# AudioStream_v2.net
KiCad netlist of a schematic drawn in EAGLE
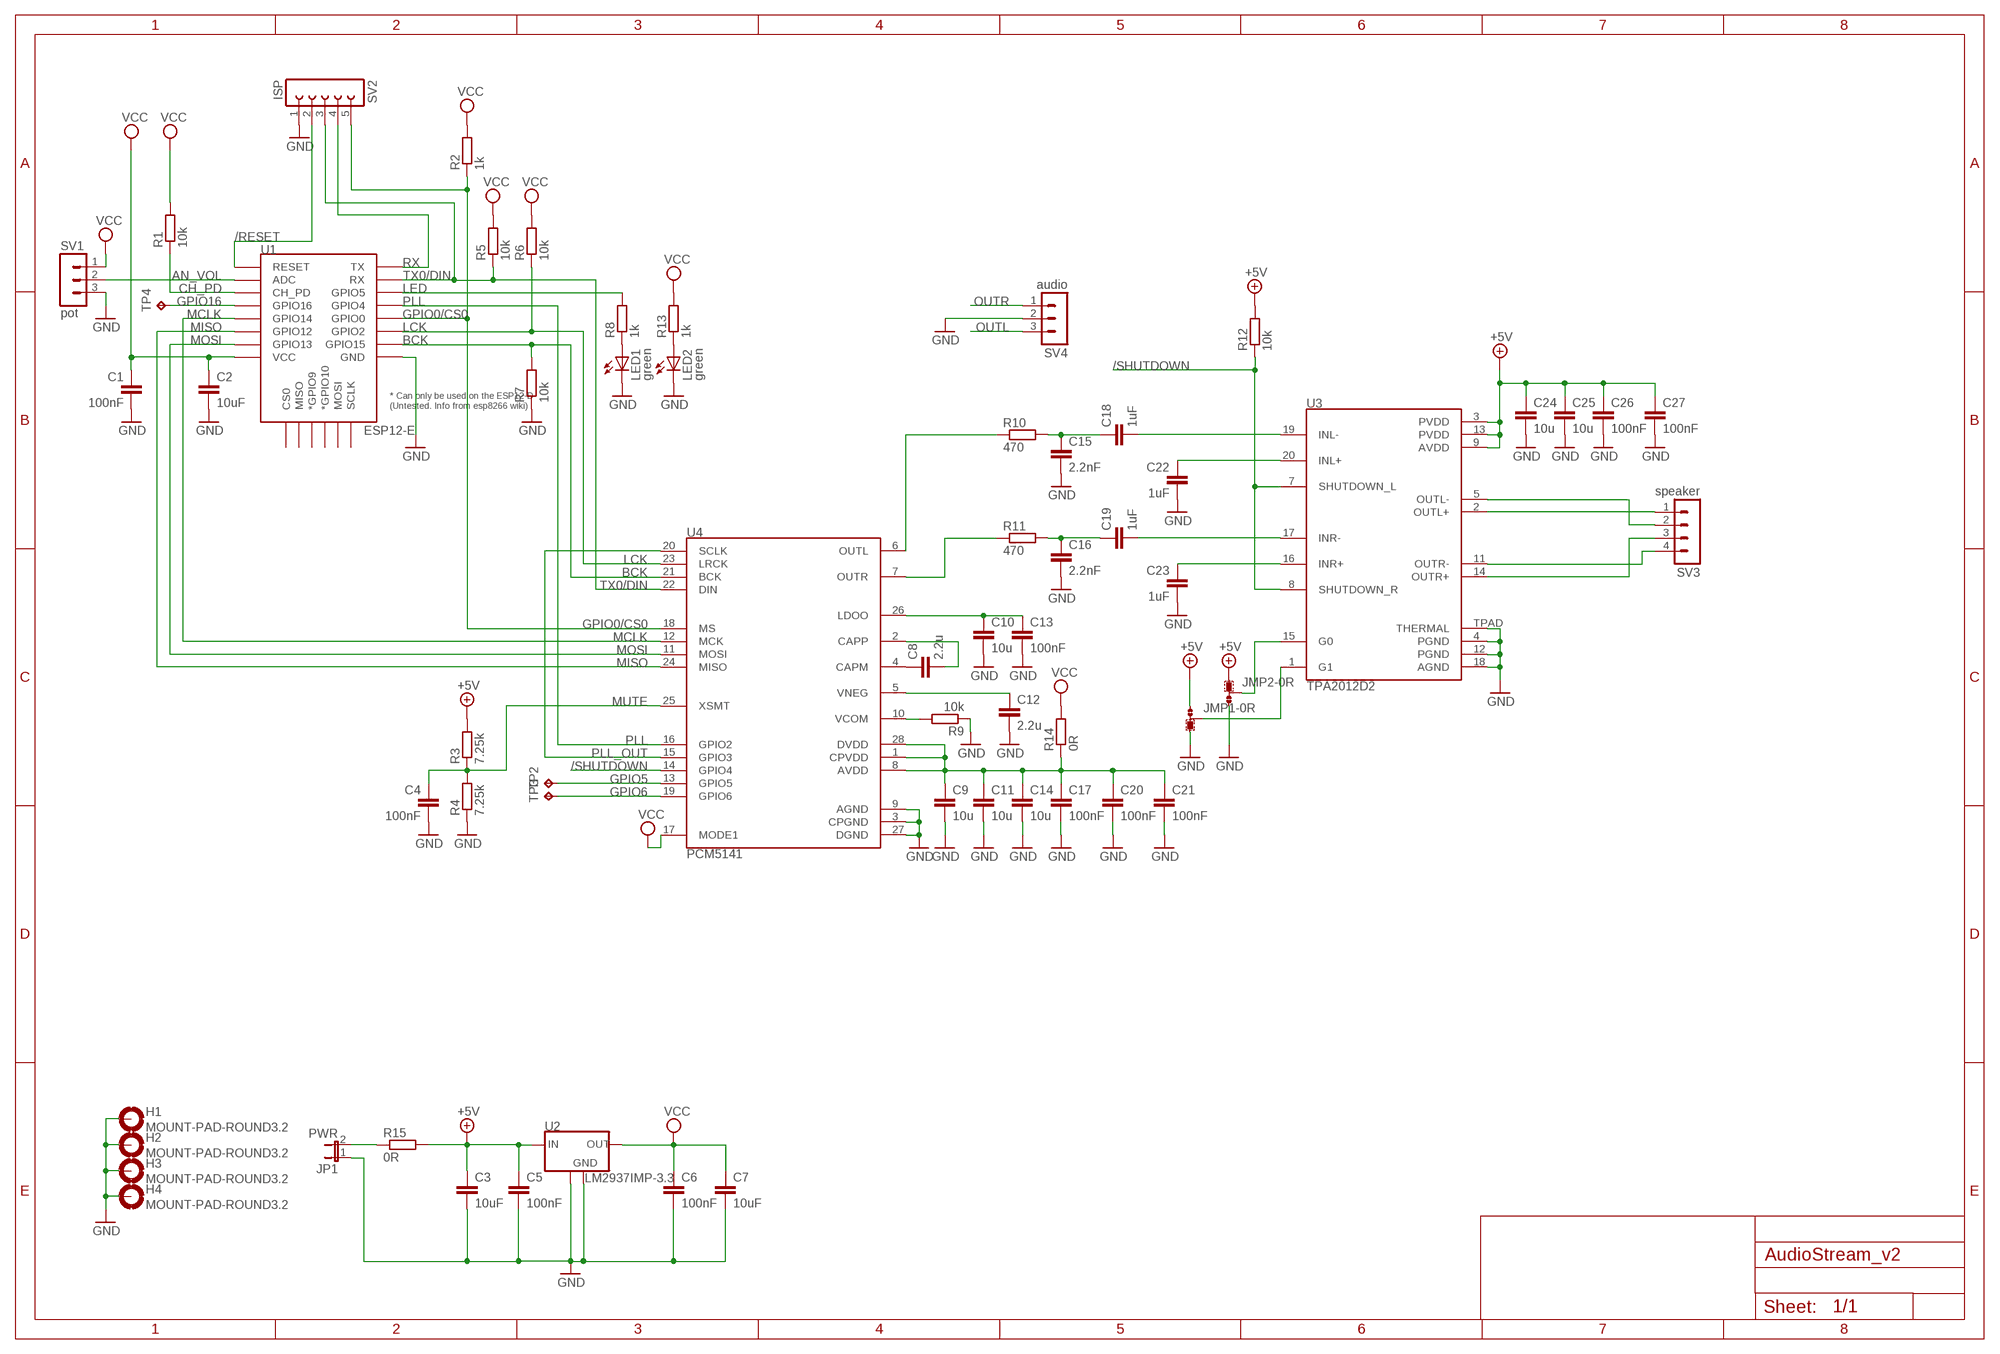
[diagram p0: schematic, sheet 1]

(export (version "E")
  (design (tool "Eeschema 10.0.6"))
  (components
    (comp (ref "C1")
      (value "100nF")
      (footprint "eagle-import:C0805")
      (libsource (lib "eagle-import") (part "C-EUC0805"))
    )
    (comp (ref "C2")
      (value "10uF")
      (footprint "eagle-import:C1210")
      (libsource (lib "eagle-import") (part "C-EUC1210"))
    )
    (comp (ref "C3")
      (value "10uF")
      (footprint "eagle-import:C3216")
      (libsource (lib "eagle-import") (part "C-EUC3216"))
    )
    (comp (ref "C4")
      (value "100nF")
      (footprint "eagle-import:C0603")
      (libsource (lib "eagle-import") (part "C-EUC0603"))
    )
    (comp (ref "C5")
      (value "100nF")
      (footprint "eagle-import:C0805")
      (libsource (lib "eagle-import") (part "C-EUC0805"))
    )
    (comp (ref "C6")
      (value "100nF")
      (footprint "eagle-import:C0805")
      (libsource (lib "eagle-import") (part "C-EUC0805"))
    )
    (comp (ref "C7")
      (value "10uF")
      (footprint "eagle-import:C3216")
      (libsource (lib "eagle-import") (part "C-EUC3216"))
    )
    (comp (ref "C8")
      (value "2.2u")
      (footprint "eagle-import:C0805")
      (libsource (lib "eagle-import") (part "C-EUC0805"))
    )
    (comp (ref "C9")
      (value "10u")
      (footprint "eagle-import:C3216")
      (libsource (lib "eagle-import") (part "C-EUC3216"))
    )
    (comp (ref "C10")
      (value "10u")
      (footprint "eagle-import:C3216")
      (libsource (lib "eagle-import") (part "C-EUC3216"))
    )
    (comp (ref "C11")
      (value "10u")
      (footprint "eagle-import:C3216")
      (libsource (lib "eagle-import") (part "C-EUC3216"))
    )
    (comp (ref "C12")
      (value "2.2u")
      (footprint "eagle-import:C0805")
      (libsource (lib "eagle-import") (part "C-EUC0805"))
    )
    (comp (ref "C13")
      (value "100nF")
      (footprint "eagle-import:C0805")
      (libsource (lib "eagle-import") (part "C-EUC0805"))
    )
    (comp (ref "C14")
      (value "10u")
      (footprint "eagle-import:C3216")
      (libsource (lib "eagle-import") (part "C-EUC3216"))
    )
    (comp (ref "C15")
      (value "2.2nF")
      (footprint "eagle-import:C0603")
      (libsource (lib "eagle-import") (part "C-EUC0603"))
    )
    (comp (ref "C16")
      (value "2.2nF")
      (footprint "eagle-import:C0603")
      (libsource (lib "eagle-import") (part "C-EUC0603"))
    )
    (comp (ref "C17")
      (value "100nF")
      (footprint "eagle-import:C0805")
      (libsource (lib "eagle-import") (part "C-EUC0805"))
    )
    (comp (ref "C18")
      (value "1uF")
      (footprint "eagle-import:C0805")
      (libsource (lib "eagle-import") (part "C-EUC0805"))
    )
    (comp (ref "C19")
      (value "1uF")
      (footprint "eagle-import:C0805")
      (libsource (lib "eagle-import") (part "C-EUC0805"))
    )
    (comp (ref "C20")
      (value "100nF")
      (footprint "eagle-import:C0805")
      (libsource (lib "eagle-import") (part "C-EUC0805"))
    )
    (comp (ref "C21")
      (value "100nF")
      (footprint "eagle-import:C0805")
      (libsource (lib "eagle-import") (part "C-EUC0805"))
    )
    (comp (ref "C22")
      (value "1uF")
      (footprint "eagle-import:C0805")
      (libsource (lib "eagle-import") (part "C-EUC0805"))
    )
    (comp (ref "C23")
      (value "1uF")
      (footprint "eagle-import:C0805")
      (libsource (lib "eagle-import") (part "C-EUC0805"))
    )
    (comp (ref "C24")
      (value "10u")
      (footprint "eagle-import:C3216")
      (libsource (lib "eagle-import") (part "C-EUC3216"))
    )
    (comp (ref "C25")
      (value "10u")
      (footprint "eagle-import:C3216")
      (libsource (lib "eagle-import") (part "C-EUC3216"))
    )
    (comp (ref "C26")
      (value "100nF")
      (footprint "eagle-import:C0805")
      (libsource (lib "eagle-import") (part "C-EUC0805"))
    )
    (comp (ref "C27")
      (value "100nF")
      (footprint "eagle-import:C0805")
      (libsource (lib "eagle-import") (part "C-EUC0805"))
    )
    (comp (ref "H1")
      (value "MOUNT-PAD-ROUND3.2")
      (footprint "eagle-import:3,2-PAD")
      (libsource (lib "eagle-import") (part "MOUNT-PAD-ROUND3.2"))
    )
    (comp (ref "H2")
      (value "MOUNT-PAD-ROUND3.2")
      (footprint "eagle-import:3,2-PAD")
      (libsource (lib "eagle-import") (part "MOUNT-PAD-ROUND3.2"))
    )
    (comp (ref "H3")
      (value "MOUNT-PAD-ROUND3.2")
      (footprint "eagle-import:3,2-PAD")
      (libsource (lib "eagle-import") (part "MOUNT-PAD-ROUND3.2"))
    )
    (comp (ref "H4")
      (value "MOUNT-PAD-ROUND3.2")
      (footprint "eagle-import:3,2-PAD")
      (libsource (lib "eagle-import") (part "MOUNT-PAD-ROUND3.2"))
    )
    (comp (ref "JMP1")
      (value "0R-JUMPA")
      (footprint "eagle-import:A0R-JMP")
      (libsource (lib "eagle-import") (part "0R-JUMPA"))
    )
    (comp (ref "JMP2")
      (value "0R-JUMPA")
      (footprint "eagle-import:A0R-JMP")
      (libsource (lib "eagle-import") (part "0R-JUMPA"))
    )
    (comp (ref "JP1")
      (value "PWR")
      (footprint "eagle-import:JP1")
      (libsource (lib "eagle-import") (part "JP1E"))
    )
    (comp (ref "LED1")
      (value "green")
      (footprint "eagle-import:CHIPLED_0805")
      (libsource (lib "eagle-import") (part "LEDCHIPLED_0805"))
    )
    (comp (ref "LED2")
      (value "green")
      (footprint "eagle-import:CHIPLED_0805")
      (libsource (lib "eagle-import") (part "LEDCHIPLED_0805"))
    )
    (comp (ref "R1")
      (value "10k")
      (footprint "eagle-import:R0603")
      (libsource (lib "eagle-import") (part "R-EU_R0603"))
    )
    (comp (ref "R2")
      (value "1k")
      (footprint "eagle-import:R0603")
      (libsource (lib "eagle-import") (part "R-EU_R0603"))
    )
    (comp (ref "R3")
      (value "7.25k")
      (footprint "eagle-import:R0603")
      (libsource (lib "eagle-import") (part "R-EU_R0603"))
    )
    (comp (ref "R4")
      (value "7.25k")
      (footprint "eagle-import:R0603")
      (libsource (lib "eagle-import") (part "R-EU_R0603"))
    )
    (comp (ref "R5")
      (value "10k")
      (footprint "eagle-import:R0603")
      (libsource (lib "eagle-import") (part "R-EU_R0603"))
    )
    (comp (ref "R6")
      (value "10k")
      (footprint "eagle-import:R0603")
      (libsource (lib "eagle-import") (part "R-EU_R0603"))
    )
    (comp (ref "R7")
      (value "10k")
      (footprint "eagle-import:R0603")
      (libsource (lib "eagle-import") (part "R-EU_R0603"))
    )
    (comp (ref "R8")
      (value "1k")
      (footprint "eagle-import:R0603")
      (libsource (lib "eagle-import") (part "R-EU_R0603"))
    )
    (comp (ref "R9")
      (value "10k")
      (footprint "eagle-import:R0603")
      (libsource (lib "eagle-import") (part "R-EU_R0603"))
    )
    (comp (ref "R10")
      (value "470")
      (footprint "eagle-import:R0603")
      (libsource (lib "eagle-import") (part "R-EU_R0603"))
    )
    (comp (ref "R11")
      (value "470")
      (footprint "eagle-import:R0603")
      (libsource (lib "eagle-import") (part "R-EU_R0603"))
    )
    (comp (ref "R12")
      (value "10k")
      (footprint "eagle-import:R0603")
      (libsource (lib "eagle-import") (part "R-EU_R0603"))
    )
    (comp (ref "R13")
      (value "1k")
      (footprint "eagle-import:R0603")
      (libsource (lib "eagle-import") (part "R-EU_R0603"))
    )
    (comp (ref "R14")
      (value "0R")
      (footprint "eagle-import:R0805")
      (libsource (lib "eagle-import") (part "R-EU_R0805"))
    )
    (comp (ref "R15")
      (value "0R")
      (footprint "eagle-import:R0805")
      (libsource (lib "eagle-import") (part "R-EU_R0805"))
    )
    (comp (ref "SV1")
      (value "pot")
      (footprint "eagle-import:MA03-1")
      (libsource (lib "eagle-import") (part "MA03-1"))
    )
    (comp (ref "SV2")
      (value "ISP")
      (footprint "eagle-import:FE05-1")
      (libsource (lib "eagle-import") (part "FE05-1"))
    )
    (comp (ref "SV3")
      (value "speaker")
      (footprint "eagle-import:MA04-1")
      (libsource (lib "eagle-import") (part "MA04-1"))
    )
    (comp (ref "SV4")
      (value "audio")
      (footprint "eagle-import:MA03-1")
      (libsource (lib "eagle-import") (part "MA03-1"))
    )
    (comp (ref "TP2")
      (value "TPTP10R")
      (footprint "eagle-import:TP10R")
      (libsource (lib "eagle-import") (part "TPTP10R"))
    )
    (comp (ref "TP3")
      (value "TPTP10R")
      (footprint "eagle-import:TP10R")
      (libsource (lib "eagle-import") (part "TPTP10R"))
    )
    (comp (ref "TP4")
      (value "TPTP10R")
      (footprint "eagle-import:TP10R")
      (libsource (lib "eagle-import") (part "TPTP10R"))
    )
    (comp (ref "U1")
      (value "ESP12-E")
      (footprint "eagle-import:ESP12E-SMD")
      (libsource (lib "eagle-import") (part "ESP12ESMD"))
    )
    (comp (ref "U2")
      (value "LM2937IMP-3.3")
      (footprint "eagle-import:SOT223")
      (libsource (lib "eagle-import") (part "LM2937IMP-X.X"))
    )
    (comp (ref "U3")
      (value "TPA2012D2")
      (footprint "eagle-import:QFN50P400X400X100-21N")
      (libsource (lib "eagle-import") (part "TPA2012D2"))
    )
    (comp (ref "U4")
      (value "PCM5141")
      (footprint "eagle-import:PW_R-PDSO-G28")
      (libsource (lib "eagle-import") (part "PCM5141"))
    )
  )
  (nets
    (net (code "1") (name "+5V") (class "Default")
      (node (ref "C24") (pin "1") (pinfunction "1_1") (pintype "passive"))
      (node (ref "C25") (pin "1") (pinfunction "1_1") (pintype "passive"))
      (node (ref "C26") (pin "1") (pinfunction "1_1") (pintype "passive"))
      (node (ref "C27") (pin "1") (pinfunction "1_1") (pintype "passive"))
      (node (ref "C3") (pin "1") (pinfunction "1_1") (pintype "passive"))
      (node (ref "C5") (pin "1") (pinfunction "1_1") (pintype "passive"))
      (node (ref "JMP1") (pin "1") (pinfunction "1_1") (pintype "passive"))
      (node (ref "JMP2") (pin "1") (pinfunction "1_1") (pintype "passive"))
      (node (ref "R12") (pin "2") (pinfunction "2_2") (pintype "passive"))
      (node (ref "R15") (pin "2") (pinfunction "2_2") (pintype "passive"))
      (node (ref "R3") (pin "2") (pinfunction "2_2") (pintype "passive"))
      (node (ref "U2") (pin "1") (pinfunction "IN_1") (pintype "input"))
      (node (ref "U3") (pin "13") (pinfunction "PVDD_13") (pintype "power_in"))
      (node (ref "U3") (pin "3") (pinfunction "PVDD_3") (pintype "power_in"))
      (node (ref "U3") (pin "9") (pinfunction "AVDD_9") (pintype "power_in"))
    )
    (net (code "2") (name "/AN_VOL") (class "Default")
      (node (ref "SV1") (pin "2") (pinfunction "2_2") (pintype "passive"))
      (node (ref "U1") (pin "ADC") (pinfunction "ADC_ADC") (pintype "bidirectional"))
    )
    (net (code "3") (name "/BCK") (class "Default")
      (node (ref "R7") (pin "2") (pinfunction "2_2") (pintype "passive"))
      (node (ref "U1") (pin "GPIO15") (pinfunction "GPIO15_GPIO15") (pintype "bidirectional"))
      (node (ref "U4") (pin "21") (pinfunction "BCK_21") (pintype "input"))
    )
    (net (code "4") (name "/CH_PD") (class "Default")
      (node (ref "R1") (pin "1") (pinfunction "1_1") (pintype "passive"))
      (node (ref "U1") (pin "CH_PD") (pinfunction "CH_PD_CH_PD") (pintype "bidirectional"))
    )
    (net (code "5") (name "/GPIO0{slash}CS0") (class "Default")
      (node (ref "R2") (pin "1") (pinfunction "1_1") (pintype "passive"))
      (node (ref "SV2") (pin "5") (pinfunction "5_5") (pintype "passive"))
      (node (ref "U1") (pin "GPIO0") (pinfunction "GPIO0_GPIO0") (pintype "bidirectional"))
      (node (ref "U4") (pin "18") (pinfunction "MS_18") (pintype "input"))
    )
    (net (code "6") (name "/GPIO5") (class "Default")
      (node (ref "TP2") (pin "TP") (pinfunction "TP_TP") (pintype "input"))
      (node (ref "U4") (pin "13") (pinfunction "GPIO5_13") (pintype "bidirectional"))
    )
    (net (code "7") (name "/GPIO6") (class "Default")
      (node (ref "TP3") (pin "TP") (pinfunction "TP_TP") (pintype "input"))
      (node (ref "U4") (pin "19") (pinfunction "GPIO6_19") (pintype "bidirectional"))
    )
    (net (code "8") (name "/GPIO16") (class "Default")
      (node (ref "TP4") (pin "TP") (pinfunction "TP_TP") (pintype "input"))
      (node (ref "U1") (pin "GPIO16") (pinfunction "GPIO16_GPIO16") (pintype "bidirectional"))
    )
    (net (code "9") (name "/LCK") (class "Default")
      (node (ref "R6") (pin "1") (pinfunction "1_1") (pintype "passive"))
      (node (ref "U1") (pin "GPIO2") (pinfunction "GPIO2_GPIO2") (pintype "bidirectional"))
      (node (ref "U4") (pin "23") (pinfunction "LRCK_23") (pintype "input"))
    )
    (net (code "10") (name "/LED") (class "Default")
      (node (ref "R8") (pin "2") (pinfunction "2_2") (pintype "passive"))
      (node (ref "U1") (pin "GPIO5") (pinfunction "GPIO5_GPIO5") (pintype "bidirectional"))
    )
    (net (code "11") (name "/MCLK") (class "Default")
      (node (ref "U1") (pin "GPIO14") (pinfunction "GPIO14_GPIO14") (pintype "bidirectional"))
      (node (ref "U4") (pin "12") (pinfunction "MCK_12") (pintype "input"))
    )
    (net (code "12") (name "/MISO") (class "Default")
      (node (ref "U1") (pin "GPIO12") (pinfunction "GPIO12_GPIO12") (pintype "bidirectional"))
      (node (ref "U4") (pin "24") (pinfunction "MISO_24") (pintype "output"))
    )
    (net (code "13") (name "/MOSI") (class "Default")
      (node (ref "U1") (pin "GPIO13") (pinfunction "GPIO13_GPIO13") (pintype "bidirectional"))
      (node (ref "U4") (pin "11") (pinfunction "MOSI_11") (pintype "input"))
    )
    (net (code "14") (name "/MUTE") (class "Default")
      (node (ref "C4") (pin "1") (pinfunction "1_1") (pintype "passive"))
      (node (ref "R3") (pin "1") (pinfunction "1_1") (pintype "passive"))
      (node (ref "R4") (pin "2") (pinfunction "2_2") (pintype "passive"))
      (node (ref "U4") (pin "25") (pinfunction "XSMT_25") (pintype "input"))
    )
    (net (code "15") (name "/OUTL") (class "Default")
      (node (ref "C15") (pin "1") (pinfunction "1_1") (pintype "passive"))
      (node (ref "C18") (pin "1") (pinfunction "1_1") (pintype "passive"))
      (node (ref "R10") (pin "2") (pinfunction "2_2") (pintype "passive"))
      (node (ref "SV4") (pin "3") (pinfunction "3_3") (pintype "passive"))
    )
    (net (code "16") (name "/OUTR") (class "Default")
      (node (ref "C16") (pin "1") (pinfunction "1_1") (pintype "passive"))
      (node (ref "C19") (pin "1") (pinfunction "1_1") (pintype "passive"))
      (node (ref "R11") (pin "2") (pinfunction "2_2") (pintype "passive"))
      (node (ref "SV4") (pin "1") (pinfunction "1_1") (pintype "passive"))
    )
    (net (code "17") (name "/PLL") (class "Default")
      (node (ref "U1") (pin "GPIO4") (pinfunction "GPIO4_GPIO4") (pintype "bidirectional"))
      (node (ref "U4") (pin "16") (pinfunction "GPIO2_16") (pintype "bidirectional"))
    )
    (net (code "18") (name "/PLL_OUT") (class "Default")
      (node (ref "U4") (pin "15") (pinfunction "GPIO3_15") (pintype "bidirectional"))
      (node (ref "U4") (pin "20") (pinfunction "SCLK_20") (pintype "input"))
    )
    (net (code "19") (name "/RX") (class "Default")
      (node (ref "SV2") (pin "4") (pinfunction "4_4") (pintype "passive"))
      (node (ref "U1") (pin "TXD0") (pinfunction "TX_TXD0") (pintype "bidirectional"))
    )
    (net (code "20") (name "/TX0{slash}DIN") (class "Default")
      (node (ref "R5") (pin "1") (pinfunction "1_1") (pintype "passive"))
      (node (ref "SV2") (pin "3") (pinfunction "3_3") (pintype "passive"))
      (node (ref "U1") (pin "RXD0") (pinfunction "RX_RXD0") (pintype "bidirectional"))
      (node (ref "U4") (pin "22") (pinfunction "DIN_22") (pintype "input"))
    )
    (net (code "21") (name "/{slash}RESET") (class "Default")
      (node (ref "SV2") (pin "2") (pinfunction "2_2") (pintype "passive"))
      (node (ref "U1") (pin "RESET") (pinfunction "RESET_RESET") (pintype "bidirectional"))
    )
    (net (code "22") (name "/{slash}SHUTDOWN") (class "Default")
      (node (ref "R12") (pin "1") (pinfunction "1_1") (pintype "passive"))
      (node (ref "U3") (pin "7") (pinfunction "SHUTDOWN_L_7") (pintype "input"))
      (node (ref "U3") (pin "8") (pinfunction "SHUTDOWN_R_8") (pintype "input"))
      (node (ref "U4") (pin "14") (pinfunction "GPIO4_14") (pintype "bidirectional"))
    )
    (net (code "23") (name "GND") (class "Default")
      (node (ref "C1") (pin "2") (pinfunction "2_2") (pintype "passive"))
      (node (ref "C10") (pin "2") (pinfunction "2_2") (pintype "passive"))
      (node (ref "C11") (pin "2") (pinfunction "2_2") (pintype "passive"))
      (node (ref "C12") (pin "2") (pinfunction "2_2") (pintype "passive"))
      (node (ref "C13") (pin "2") (pinfunction "2_2") (pintype "passive"))
      (node (ref "C14") (pin "2") (pinfunction "2_2") (pintype "passive"))
      (node (ref "C15") (pin "2") (pinfunction "2_2") (pintype "passive"))
      (node (ref "C16") (pin "2") (pinfunction "2_2") (pintype "passive"))
      (node (ref "C17") (pin "2") (pinfunction "2_2") (pintype "passive"))
      (node (ref "C2") (pin "2") (pinfunction "2_2") (pintype "passive"))
      (node (ref "C20") (pin "2") (pinfunction "2_2") (pintype "passive"))
      (node (ref "C21") (pin "2") (pinfunction "2_2") (pintype "passive"))
      (node (ref "C22") (pin "2") (pinfunction "2_2") (pintype "passive"))
      (node (ref "C23") (pin "2") (pinfunction "2_2") (pintype "passive"))
      (node (ref "C24") (pin "2") (pinfunction "2_2") (pintype "passive"))
      (node (ref "C25") (pin "2") (pinfunction "2_2") (pintype "passive"))
      (node (ref "C26") (pin "2") (pinfunction "2_2") (pintype "passive"))
      (node (ref "C27") (pin "2") (pinfunction "2_2") (pintype "passive"))
      (node (ref "C3") (pin "2") (pinfunction "2_2") (pintype "passive"))
      (node (ref "C4") (pin "2") (pinfunction "2_2") (pintype "passive"))
      (node (ref "C5") (pin "2") (pinfunction "2_2") (pintype "passive"))
      (node (ref "C6") (pin "2") (pinfunction "2_2") (pintype "passive"))
      (node (ref "C7") (pin "2") (pinfunction "2_2") (pintype "passive"))
      (node (ref "C9") (pin "2") (pinfunction "2_2") (pintype "passive"))
      (node (ref "H1") (pin "B3,2") (pinfunction "MOUNT_B3,2") (pintype "passive"))
      (node (ref "H2") (pin "B3,2") (pinfunction "MOUNT_B3,2") (pintype "passive"))
      (node (ref "H3") (pin "B3,2") (pinfunction "MOUNT_B3,2") (pintype "passive"))
      (node (ref "H4") (pin "B3,2") (pinfunction "MOUNT_B3,2") (pintype "passive"))
      (node (ref "JMP1") (pin "3") (pinfunction "3_3") (pintype "passive"))
      (node (ref "JMP2") (pin "3") (pinfunction "3_3") (pintype "passive"))
      (node (ref "JP1") (pin "1") (pinfunction "1_1") (pintype "passive"))
      (node (ref "LED1") (pin "C") (pinfunction "C_C") (pintype "passive"))
      (node (ref "LED2") (pin "C") (pinfunction "C_C") (pintype "passive"))
      (node (ref "R4") (pin "1") (pinfunction "1_1") (pintype "passive"))
      (node (ref "R7") (pin "1") (pinfunction "1_1") (pintype "passive"))
      (node (ref "R9") (pin "1") (pinfunction "1_1") (pintype "passive"))
      (node (ref "SV1") (pin "3") (pinfunction "3_3") (pintype "passive"))
      (node (ref "SV2") (pin "1") (pinfunction "1_1") (pintype "passive"))
      (node (ref "SV4") (pin "2") (pinfunction "2_2") (pintype "passive"))
      (node (ref "U1") (pin "GND") (pinfunction "GND_GND") (pintype "bidirectional"))
      (node (ref "U2") (pin "2") (pinfunction "GND_2") (pintype "input"))
      (node (ref "U2") (pin "4") (pinfunction "GND_4") (pintype "input"))
      (node (ref "U3") (pin "12") (pinfunction "PGND_12") (pintype "power_in"))
      (node (ref "U3") (pin "18") (pinfunction "AGND_18") (pintype "power_in"))
      (node (ref "U3") (pin "4") (pinfunction "PGND_4") (pintype "power_in"))
      (node (ref "U3") (pin "TPAD") (pinfunction "THERMAL_TPAD") (pintype "power_in"))
      (node (ref "U4") (pin "27") (pinfunction "DGND_27") (pintype "power_in"))
      (node (ref "U4") (pin "3") (pinfunction "CPGND_3") (pintype "power_in"))
      (node (ref "U4") (pin "9") (pinfunction "AGND_9") (pintype "power_in"))
    )
    (net (code "24") (name "Net-(JP1-Pad2)") (class "Default")
      (node (ref "JP1") (pin "2") (pinfunction "2_2") (pintype "passive"))
      (node (ref "R15") (pin "1") (pinfunction "1_1") (pintype "passive"))
    )
    (net (code "25") (name "Net-(LED1-PadA)") (class "Default")
      (node (ref "LED1") (pin "A") (pinfunction "A_A") (pintype "passive"))
      (node (ref "R8") (pin "1") (pinfunction "1_1") (pintype "passive"))
    )
    (net (code "26") (name "Net-(LED2-PadA)") (class "Default")
      (node (ref "LED2") (pin "A") (pinfunction "A_A") (pintype "passive"))
      (node (ref "R13") (pin "1") (pinfunction "1_1") (pintype "passive"))
    )
    (net (code "27") (name "Net-(U3-G0)") (class "Default")
      (node (ref "JMP2") (pin "2") (pinfunction "2_2") (pintype "passive"))
      (node (ref "U3") (pin "15") (pinfunction "G0_15") (pintype "input"))
    )
    (net (code "28") (name "Net-(U3-G1)") (class "Default")
      (node (ref "JMP1") (pin "2") (pinfunction "2_2") (pintype "passive"))
      (node (ref "U3") (pin "1") (pinfunction "G1_1") (pintype "input"))
    )
    (net (code "29") (name "Net-(U3-INL+)") (class "Default")
      (node (ref "C22") (pin "1") (pinfunction "1_1") (pintype "passive"))
      (node (ref "U3") (pin "20") (pinfunction "INL+_20") (pintype "input"))
    )
    (net (code "30") (name "Net-(U3-INL-)") (class "Default")
      (node (ref "C18") (pin "2") (pinfunction "2_2") (pintype "passive"))
      (node (ref "U3") (pin "19") (pinfunction "INL-_19") (pintype "input"))
    )
    (net (code "31") (name "Net-(U3-INR+)") (class "Default")
      (node (ref "C23") (pin "1") (pinfunction "1_1") (pintype "passive"))
      (node (ref "U3") (pin "16") (pinfunction "INR+_16") (pintype "input"))
    )
    (net (code "32") (name "Net-(U3-INR-)") (class "Default")
      (node (ref "C19") (pin "2") (pinfunction "2_2") (pintype "passive"))
      (node (ref "U3") (pin "17") (pinfunction "INR-_17") (pintype "input"))
    )
    (net (code "33") (name "Net-(U3-OUTL+)") (class "Default")
      (node (ref "SV3") (pin "1") (pinfunction "1_1") (pintype "passive"))
      (node (ref "U3") (pin "2") (pinfunction "OUTL+_2") (pintype "output"))
    )
    (net (code "34") (name "Net-(U3-OUTL-)") (class "Default")
      (node (ref "SV3") (pin "2") (pinfunction "2_2") (pintype "passive"))
      (node (ref "U3") (pin "5") (pinfunction "OUTL-_5") (pintype "output"))
    )
    (net (code "35") (name "Net-(U3-OUTR+)") (class "Default")
      (node (ref "SV3") (pin "3") (pinfunction "3_3") (pintype "passive"))
      (node (ref "U3") (pin "14") (pinfunction "OUTR+_14") (pintype "output"))
    )
    (net (code "36") (name "Net-(U3-OUTR-)") (class "Default")
      (node (ref "SV3") (pin "4") (pinfunction "4_4") (pintype "passive"))
      (node (ref "U3") (pin "11") (pinfunction "OUTR-_11") (pintype "output"))
    )
    (net (code "37") (name "Net-(U4-AVDD)") (class "Default")
      (node (ref "C11") (pin "1") (pinfunction "1_1") (pintype "passive"))
      (node (ref "C14") (pin "1") (pinfunction "1_1") (pintype "passive"))
      (node (ref "C17") (pin "1") (pinfunction "1_1") (pintype "passive"))
      (node (ref "C20") (pin "1") (pinfunction "1_1") (pintype "passive"))
      (node (ref "C21") (pin "1") (pinfunction "1_1") (pintype "passive"))
      (node (ref "C9") (pin "1") (pinfunction "1_1") (pintype "passive"))
      (node (ref "R14") (pin "1") (pinfunction "1_1") (pintype "passive"))
      (node (ref "U4") (pin "1") (pinfunction "CPVDD_1") (pintype "power_in"))
      (node (ref "U4") (pin "28") (pinfunction "DVDD_28") (pintype "power_in"))
      (node (ref "U4") (pin "8") (pinfunction "AVDD_8") (pintype "power_in"))
    )
    (net (code "38") (name "Net-(U4-CAPM)") (class "Default")
      (node (ref "C8") (pin "1") (pinfunction "1_1") (pintype "passive"))
      (node (ref "U4") (pin "4") (pinfunction "CAPM_4") (pintype "passive"))
    )
    (net (code "39") (name "Net-(U4-CAPP)") (class "Default")
      (node (ref "C8") (pin "2") (pinfunction "2_2") (pintype "passive"))
      (node (ref "U4") (pin "2") (pinfunction "CAPP_2") (pintype "passive"))
    )
    (net (code "40") (name "Net-(U4-LDOO)") (class "Default")
      (node (ref "C10") (pin "1") (pinfunction "1_1") (pintype "passive"))
      (node (ref "C13") (pin "1") (pinfunction "1_1") (pintype "passive"))
      (node (ref "U4") (pin "26") (pinfunction "LDOO_26") (pintype "passive"))
    )
    (net (code "41") (name "Net-(U4-OUTL)") (class "Default")
      (node (ref "R10") (pin "1") (pinfunction "1_1") (pintype "passive"))
      (node (ref "U4") (pin "6") (pinfunction "OUTL_6") (pintype "output"))
    )
    (net (code "42") (name "Net-(U4-OUTR)") (class "Default")
      (node (ref "R11") (pin "1") (pinfunction "1_1") (pintype "passive"))
      (node (ref "U4") (pin "7") (pinfunction "OUTR_7") (pintype "output"))
    )
    (net (code "43") (name "Net-(U4-VCOM)") (class "Default")
      (node (ref "R9") (pin "2") (pinfunction "2_2") (pintype "passive"))
      (node (ref "U4") (pin "10") (pinfunction "VCOM_10") (pintype "passive"))
    )
    (net (code "44") (name "Net-(U4-VNEG)") (class "Default")
      (node (ref "C12") (pin "1") (pinfunction "1_1") (pintype "passive"))
      (node (ref "U4") (pin "5") (pinfunction "VNEG_5") (pintype "passive"))
    )
    (net (code "45") (name "VCC") (class "Default")
      (node (ref "C1") (pin "1") (pinfunction "1_1") (pintype "passive"))
      (node (ref "C2") (pin "1") (pinfunction "1_1") (pintype "passive"))
      (node (ref "C6") (pin "1") (pinfunction "1_1") (pintype "passive"))
      (node (ref "C7") (pin "1") (pinfunction "1_1") (pintype "passive"))
      (node (ref "R1") (pin "2") (pinfunction "2_2") (pintype "passive"))
      (node (ref "R13") (pin "2") (pinfunction "2_2") (pintype "passive"))
      (node (ref "R14") (pin "2") (pinfunction "2_2") (pintype "passive"))
      (node (ref "R2") (pin "2") (pinfunction "2_2") (pintype "passive"))
      (node (ref "R5") (pin "2") (pinfunction "2_2") (pintype "passive"))
      (node (ref "R6") (pin "2") (pinfunction "2_2") (pintype "passive"))
      (node (ref "SV1") (pin "1") (pinfunction "1_1") (pintype "passive"))
      (node (ref "U1") (pin "VCC") (pinfunction "VCC_VCC") (pintype "bidirectional"))
      (node (ref "U2") (pin "3") (pinfunction "OUT_3") (pintype "passive"))
      (node (ref "U4") (pin "17") (pinfunction "MODE1_17") (pintype "input"))
    )
    (net (code "46") (name "unconnected-(U1-*GPIO9-PadGPIO9)") (class "Default")
      (node (ref "U1") (pin "GPIO9") (pinfunction "*GPIO9_GPIO9") (pintype "bidirectional"))
    )
    (net (code "47") (name "unconnected-(U1-*GPIO10-PadGPIO10)") (class "Default")
      (node (ref "U1") (pin "GPIO10") (pinfunction "*GPIO10_GPIO10") (pintype "bidirectional"))
    )
    (net (code "48") (name "unconnected-(U1-PadCS0)") (class "Default")
      (node (ref "U1") (pin "CS0") (pinfunction "CS0_CS0") (pintype "bidirectional"))
    )
    (net (code "49") (name "unconnected-(U1-PadMISO)") (class "Default")
      (node (ref "U1") (pin "MISO") (pinfunction "MISO_MISO") (pintype "bidirectional"))
    )
    (net (code "50") (name "unconnected-(U1-PadMOSI)") (class "Default")
      (node (ref "U1") (pin "MOSI") (pinfunction "MOSI_MOSI") (pintype "bidirectional"))
    )
    (net (code "51") (name "unconnected-(U1-PadSCLK)") (class "Default")
      (node (ref "U1") (pin "SCLK") (pinfunction "SCLK_SCLK") (pintype "bidirectional"))
    )
  )
)
